# ServoCapeBareBones.net
KiCad netlist of a schematic drawn in EAGLE
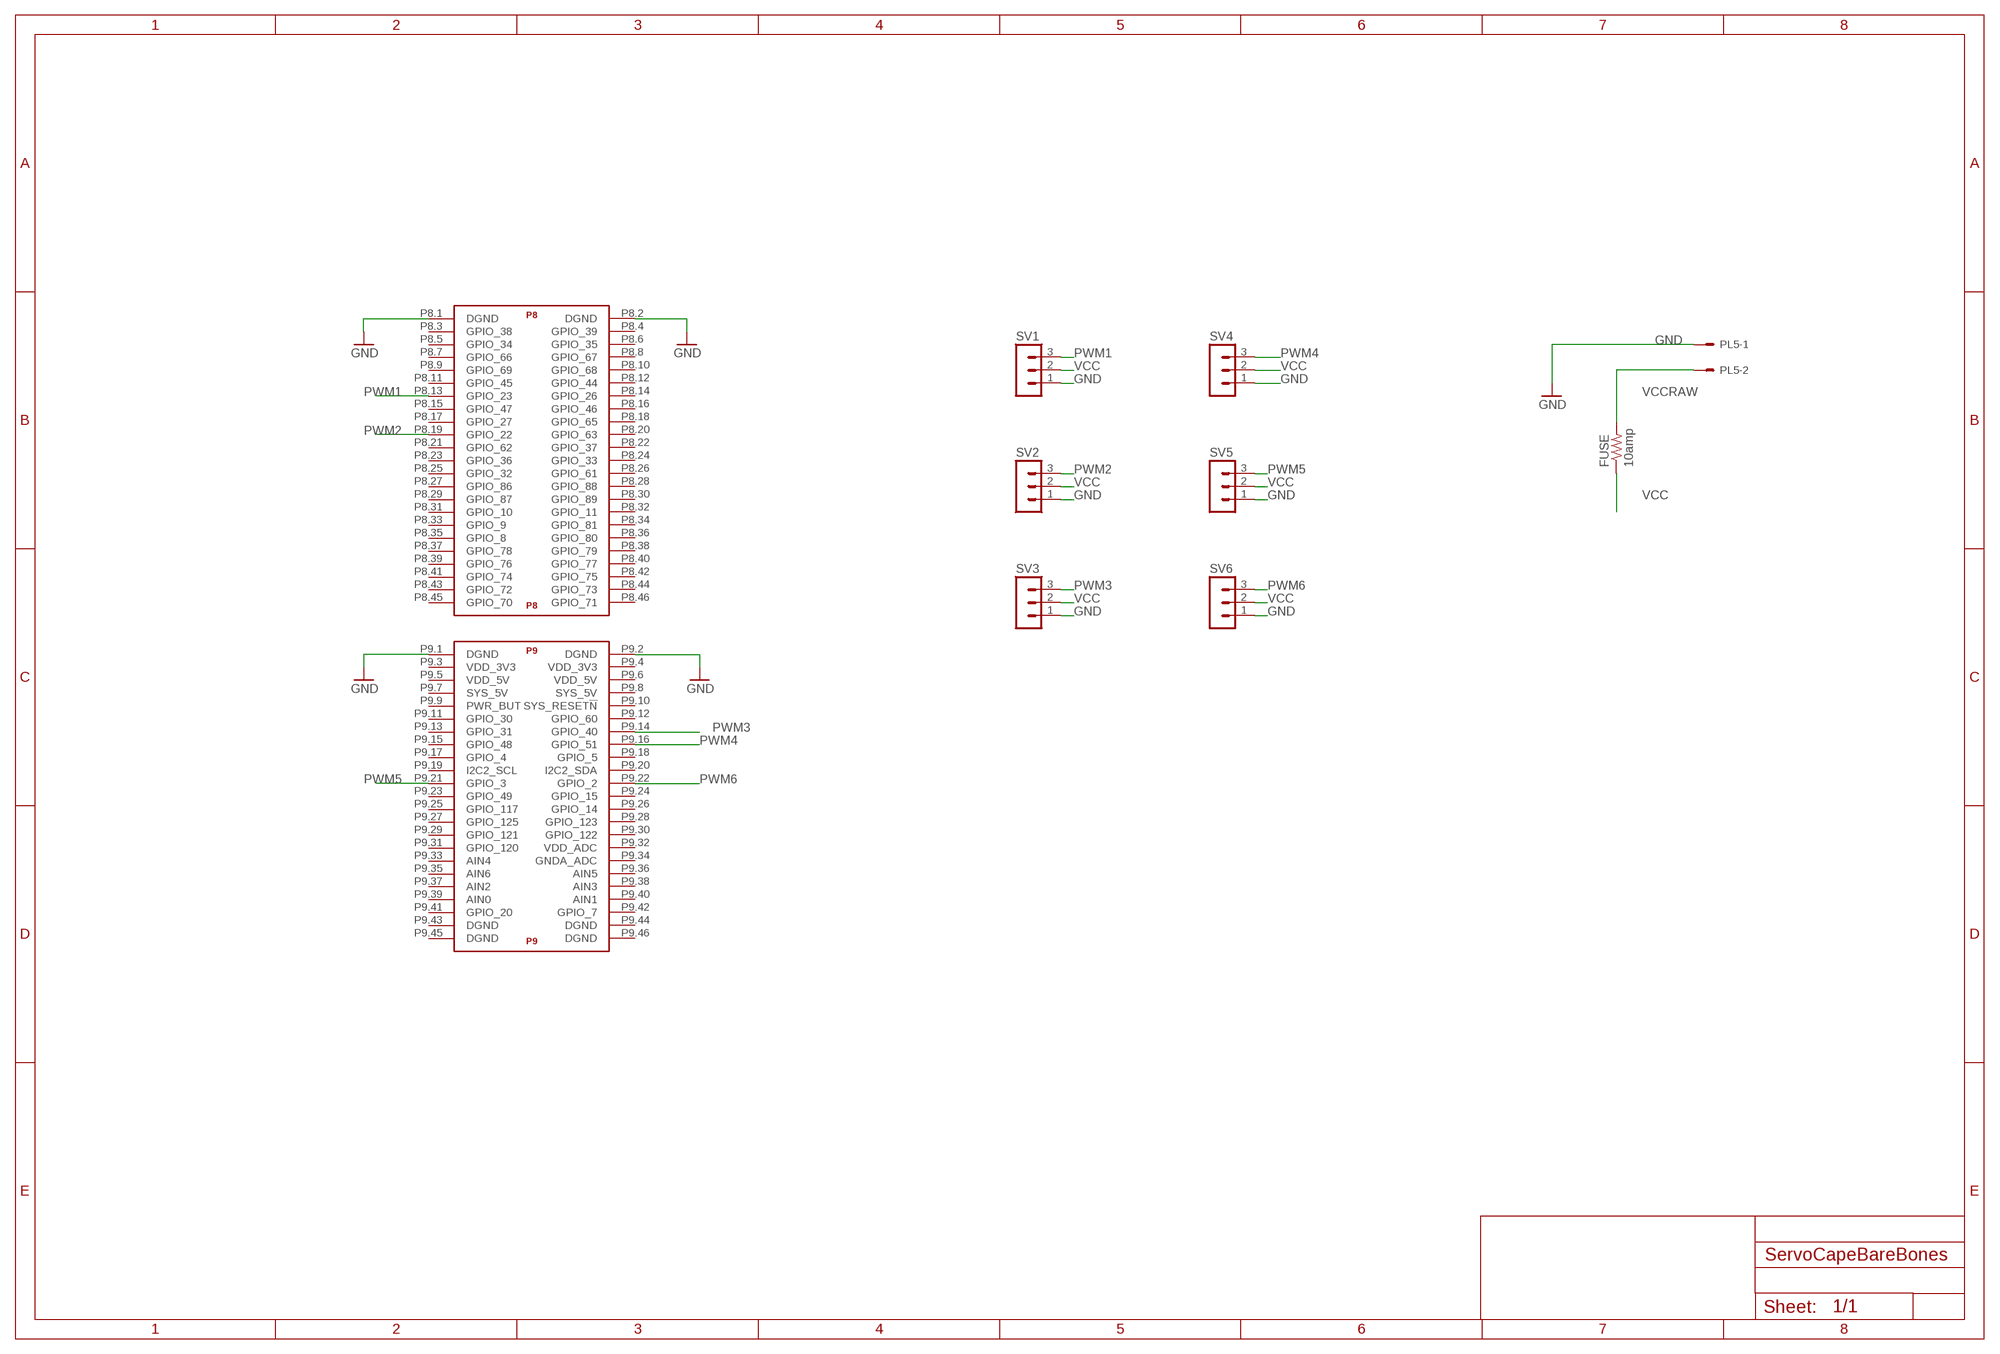
[diagram p0: schematic, sheet 1]

(export (version "E")
  (design (tool "Eeschema 10.0.6"))
  (components
    (comp (ref "FUSE")
      (value "10amp")
      (footprint "eagle-import:R1206")
      (libsource (lib "eagle-import") (part "R-US_R1206"))
    )
    (comp (ref "PL5")
      (value "555X-2H")
      (footprint "eagle-import:5569-2")
      (libsource (lib "eagle-import") (part "555X-2H"))
    )
    (comp (ref "SV1")
      (value "MA03-1")
      (footprint "eagle-import:MA03-1")
      (libsource (lib "eagle-import") (part "MA03-1"))
    )
    (comp (ref "SV2")
      (value "MA03-1")
      (footprint "eagle-import:MA03-1")
      (libsource (lib "eagle-import") (part "MA03-1"))
    )
    (comp (ref "SV3")
      (value "MA03-1")
      (footprint "eagle-import:MA03-1")
      (libsource (lib "eagle-import") (part "MA03-1"))
    )
    (comp (ref "SV4")
      (value "MA03-1")
      (footprint "eagle-import:MA03-1")
      (libsource (lib "eagle-import") (part "MA03-1"))
    )
    (comp (ref "SV5")
      (value "MA03-1")
      (footprint "eagle-import:MA03-1")
      (libsource (lib "eagle-import") (part "MA03-1"))
    )
    (comp (ref "SV6")
      (value "MA03-1")
      (footprint "eagle-import:MA03-1")
      (libsource (lib "eagle-import") (part "MA03-1"))
    )
    (comp (ref "U$1")
      (value "BEAGLE_BONE_BLACK_CAPE")
      (footprint "eagle-import:BEAGLE_BONE_BLACK_CAPE")
      (libsource (lib "eagle-import") (part "BEAGLE_BONE_BLACK_CAPE"))
    )
  )
  (nets
    (net (code "1") (name "/PWM1") (class "Default")
      (node (ref "SV1") (pin "3") (pinfunction "3_3") (pintype "passive"))
      (node (ref "U$1") (pin "P8.13") (pinfunction "GPIO_23_P8.13") (pintype "bidirectional"))
    )
    (net (code "2") (name "/PWM2") (class "Default")
      (node (ref "SV2") (pin "3") (pinfunction "3_3") (pintype "passive"))
      (node (ref "U$1") (pin "P8.19") (pinfunction "GPIO_22_P8.19") (pintype "bidirectional"))
    )
    (net (code "3") (name "/PWM3") (class "Default")
      (node (ref "SV3") (pin "3") (pinfunction "3_3") (pintype "passive"))
      (node (ref "U$1") (pin "P9.14") (pinfunction "GPIO_40_P9.14") (pintype "bidirectional"))
    )
    (net (code "4") (name "/PWM4") (class "Default")
      (node (ref "SV4") (pin "3") (pinfunction "3_3") (pintype "passive"))
      (node (ref "U$1") (pin "P9.16") (pinfunction "GPIO_51_P9.16") (pintype "bidirectional"))
    )
    (net (code "5") (name "/PWM5") (class "Default")
      (node (ref "SV5") (pin "3") (pinfunction "3_3") (pintype "passive"))
      (node (ref "U$1") (pin "P9.21") (pinfunction "GPIO_3_P9.21") (pintype "bidirectional"))
    )
    (net (code "6") (name "/PWM6") (class "Default")
      (node (ref "SV6") (pin "3") (pinfunction "3_3") (pintype "passive"))
      (node (ref "U$1") (pin "P9.22") (pinfunction "GPIO_2_P9.22") (pintype "bidirectional"))
    )
    (net (code "7") (name "/VCC") (class "Default")
      (node (ref "FUSE") (pin "1") (pinfunction "1_1") (pintype "passive"))
      (node (ref "SV1") (pin "2") (pinfunction "2_2") (pintype "passive"))
      (node (ref "SV2") (pin "2") (pinfunction "2_2") (pintype "passive"))
      (node (ref "SV3") (pin "2") (pinfunction "2_2") (pintype "passive"))
      (node (ref "SV4") (pin "2") (pinfunction "2_2") (pintype "passive"))
      (node (ref "SV5") (pin "2") (pinfunction "2_2") (pintype "passive"))
      (node (ref "SV6") (pin "2") (pinfunction "2_2") (pintype "passive"))
    )
    (net (code "8") (name "/VCCRAW") (class "Default")
      (node (ref "FUSE") (pin "2") (pinfunction "2_2") (pintype "passive"))
      (node (ref "PL5") (pin "2") (pinfunction "S_2") (pintype "passive"))
    )
    (net (code "9") (name "GND") (class "Default")
      (node (ref "PL5") (pin "1") (pinfunction "S_1") (pintype "passive"))
      (node (ref "SV1") (pin "1") (pinfunction "1_1") (pintype "passive"))
      (node (ref "SV2") (pin "1") (pinfunction "1_1") (pintype "passive"))
      (node (ref "SV3") (pin "1") (pinfunction "1_1") (pintype "passive"))
      (node (ref "SV4") (pin "1") (pinfunction "1_1") (pintype "passive"))
      (node (ref "SV5") (pin "1") (pinfunction "1_1") (pintype "passive"))
      (node (ref "SV6") (pin "1") (pinfunction "1_1") (pintype "passive"))
      (node (ref "U$1") (pin "P8.1") (pinfunction "DGND_P8.1") (pintype "bidirectional"))
      (node (ref "U$1") (pin "P8.2") (pinfunction "DGND_P8.2") (pintype "bidirectional"))
      (node (ref "U$1") (pin "P9.1") (pinfunction "DGND_P9.1") (pintype "bidirectional"))
      (node (ref "U$1") (pin "P9.2") (pinfunction "DGND_P9.2") (pintype "bidirectional"))
    )
    (net (code "10") (name "unconnected-(U$1A-GPIO_8-PadP8.35)") (class "Default")
      (node (ref "U$1") (pin "P8.35") (pinfunction "GPIO_8_P8.35") (pintype "bidirectional"))
    )
    (net (code "11") (name "unconnected-(U$1A-GPIO_9-PadP8.33)") (class "Default")
      (node (ref "U$1") (pin "P8.33") (pinfunction "GPIO_9_P8.33") (pintype "bidirectional"))
    )
    (net (code "12") (name "unconnected-(U$1A-GPIO_10-PadP8.31)") (class "Default")
      (node (ref "U$1") (pin "P8.31") (pinfunction "GPIO_10_P8.31") (pintype "bidirectional"))
    )
    (net (code "13") (name "unconnected-(U$1A-GPIO_11-PadP8.32)") (class "Default")
      (node (ref "U$1") (pin "P8.32") (pinfunction "GPIO_11_P8.32") (pintype "bidirectional"))
    )
    (net (code "14") (name "unconnected-(U$1A-GPIO_26-PadP8.14)") (class "Default")
      (node (ref "U$1") (pin "P8.14") (pinfunction "GPIO_26_P8.14") (pintype "bidirectional"))
    )
    (net (code "15") (name "unconnected-(U$1A-GPIO_27-PadP8.17)") (class "Default")
      (node (ref "U$1") (pin "P8.17") (pinfunction "GPIO_27_P8.17") (pintype "bidirectional"))
    )
    (net (code "16") (name "unconnected-(U$1A-GPIO_32-PadP8.25)") (class "Default")
      (node (ref "U$1") (pin "P8.25") (pinfunction "GPIO_32_P8.25") (pintype "bidirectional"))
    )
    (net (code "17") (name "unconnected-(U$1A-GPIO_33-PadP8.24)") (class "Default")
      (node (ref "U$1") (pin "P8.24") (pinfunction "GPIO_33_P8.24") (pintype "bidirectional"))
    )
    (net (code "18") (name "unconnected-(U$1A-GPIO_34-PadP8.5)") (class "Default")
      (node (ref "U$1") (pin "P8.5") (pinfunction "GPIO_34_P8.5") (pintype "bidirectional"))
    )
    (net (code "19") (name "unconnected-(U$1A-GPIO_35-PadP8.6)") (class "Default")
      (node (ref "U$1") (pin "P8.6") (pinfunction "GPIO_35_P8.6") (pintype "bidirectional"))
    )
    (net (code "20") (name "unconnected-(U$1A-GPIO_36-PadP8.23)") (class "Default")
      (node (ref "U$1") (pin "P8.23") (pinfunction "GPIO_36_P8.23") (pintype "bidirectional"))
    )
    (net (code "21") (name "unconnected-(U$1A-GPIO_37-PadP8.22)") (class "Default")
      (node (ref "U$1") (pin "P8.22") (pinfunction "GPIO_37_P8.22") (pintype "bidirectional"))
    )
    (net (code "22") (name "unconnected-(U$1A-GPIO_38-PadP8.3)") (class "Default")
      (node (ref "U$1") (pin "P8.3") (pinfunction "GPIO_38_P8.3") (pintype "bidirectional"))
    )
    (net (code "23") (name "unconnected-(U$1A-GPIO_39-PadP8.4)") (class "Default")
      (node (ref "U$1") (pin "P8.4") (pinfunction "GPIO_39_P8.4") (pintype "bidirectional"))
    )
    (net (code "24") (name "unconnected-(U$1A-GPIO_44-PadP8.12)") (class "Default")
      (node (ref "U$1") (pin "P8.12") (pinfunction "GPIO_44_P8.12") (pintype "bidirectional"))
    )
    (net (code "25") (name "unconnected-(U$1A-GPIO_45-PadP8.11)") (class "Default")
      (node (ref "U$1") (pin "P8.11") (pinfunction "GPIO_45_P8.11") (pintype "bidirectional"))
    )
    (net (code "26") (name "unconnected-(U$1A-GPIO_46-PadP8.16)") (class "Default")
      (node (ref "U$1") (pin "P8.16") (pinfunction "GPIO_46_P8.16") (pintype "bidirectional"))
    )
    (net (code "27") (name "unconnected-(U$1A-GPIO_47-PadP8.15)") (class "Default")
      (node (ref "U$1") (pin "P8.15") (pinfunction "GPIO_47_P8.15") (pintype "bidirectional"))
    )
    (net (code "28") (name "unconnected-(U$1A-GPIO_61-PadP8.26)") (class "Default")
      (node (ref "U$1") (pin "P8.26") (pinfunction "GPIO_61_P8.26") (pintype "bidirectional"))
    )
    (net (code "29") (name "unconnected-(U$1A-GPIO_62-PadP8.21)") (class "Default")
      (node (ref "U$1") (pin "P8.21") (pinfunction "GPIO_62_P8.21") (pintype "bidirectional"))
    )
    (net (code "30") (name "unconnected-(U$1A-GPIO_63-PadP8.20)") (class "Default")
      (node (ref "U$1") (pin "P8.20") (pinfunction "GPIO_63_P8.20") (pintype "bidirectional"))
    )
    (net (code "31") (name "unconnected-(U$1A-GPIO_65-PadP8.18)") (class "Default")
      (node (ref "U$1") (pin "P8.18") (pinfunction "GPIO_65_P8.18") (pintype "bidirectional"))
    )
    (net (code "32") (name "unconnected-(U$1A-GPIO_66-PadP8.7)") (class "Default")
      (node (ref "U$1") (pin "P8.7") (pinfunction "GPIO_66_P8.7") (pintype "bidirectional"))
    )
    (net (code "33") (name "unconnected-(U$1A-GPIO_67-PadP8.8)") (class "Default")
      (node (ref "U$1") (pin "P8.8") (pinfunction "GPIO_67_P8.8") (pintype "bidirectional"))
    )
    (net (code "34") (name "unconnected-(U$1A-GPIO_68-PadP8.10)") (class "Default")
      (node (ref "U$1") (pin "P8.10") (pinfunction "GPIO_68_P8.10") (pintype "bidirectional"))
    )
    (net (code "35") (name "unconnected-(U$1A-GPIO_69-PadP8.9)") (class "Default")
      (node (ref "U$1") (pin "P8.9") (pinfunction "GPIO_69_P8.9") (pintype "bidirectional"))
    )
    (net (code "36") (name "unconnected-(U$1A-GPIO_70-PadP8.45)") (class "Default")
      (node (ref "U$1") (pin "P8.45") (pinfunction "GPIO_70_P8.45") (pintype "bidirectional"))
    )
    (net (code "37") (name "unconnected-(U$1A-GPIO_71-PadP8.46)") (class "Default")
      (node (ref "U$1") (pin "P8.46") (pinfunction "GPIO_71_P8.46") (pintype "bidirectional"))
    )
    (net (code "38") (name "unconnected-(U$1A-GPIO_72-PadP8.43)") (class "Default")
      (node (ref "U$1") (pin "P8.43") (pinfunction "GPIO_72_P8.43") (pintype "bidirectional"))
    )
    (net (code "39") (name "unconnected-(U$1A-GPIO_73-PadP8.44)") (class "Default")
      (node (ref "U$1") (pin "P8.44") (pinfunction "GPIO_73_P8.44") (pintype "bidirectional"))
    )
    (net (code "40") (name "unconnected-(U$1A-GPIO_74-PadP8.41)") (class "Default")
      (node (ref "U$1") (pin "P8.41") (pinfunction "GPIO_74_P8.41") (pintype "bidirectional"))
    )
    (net (code "41") (name "unconnected-(U$1A-GPIO_75-PadP8.42)") (class "Default")
      (node (ref "U$1") (pin "P8.42") (pinfunction "GPIO_75_P8.42") (pintype "bidirectional"))
    )
    (net (code "42") (name "unconnected-(U$1A-GPIO_76-PadP8.39)") (class "Default")
      (node (ref "U$1") (pin "P8.39") (pinfunction "GPIO_76_P8.39") (pintype "bidirectional"))
    )
    (net (code "43") (name "unconnected-(U$1A-GPIO_77-PadP8.40)") (class "Default")
      (node (ref "U$1") (pin "P8.40") (pinfunction "GPIO_77_P8.40") (pintype "bidirectional"))
    )
    (net (code "44") (name "unconnected-(U$1A-GPIO_78-PadP8.37)") (class "Default")
      (node (ref "U$1") (pin "P8.37") (pinfunction "GPIO_78_P8.37") (pintype "bidirectional"))
    )
    (net (code "45") (name "unconnected-(U$1A-GPIO_79-PadP8.38)") (class "Default")
      (node (ref "U$1") (pin "P8.38") (pinfunction "GPIO_79_P8.38") (pintype "bidirectional"))
    )
    (net (code "46") (name "unconnected-(U$1A-GPIO_80-PadP8.36)") (class "Default")
      (node (ref "U$1") (pin "P8.36") (pinfunction "GPIO_80_P8.36") (pintype "bidirectional"))
    )
    (net (code "47") (name "unconnected-(U$1A-GPIO_81-PadP8.34)") (class "Default")
      (node (ref "U$1") (pin "P8.34") (pinfunction "GPIO_81_P8.34") (pintype "bidirectional"))
    )
    (net (code "48") (name "unconnected-(U$1A-GPIO_86-PadP8.27)") (class "Default")
      (node (ref "U$1") (pin "P8.27") (pinfunction "GPIO_86_P8.27") (pintype "bidirectional"))
    )
    (net (code "49") (name "unconnected-(U$1A-GPIO_87-PadP8.29)") (class "Default")
      (node (ref "U$1") (pin "P8.29") (pinfunction "GPIO_87_P8.29") (pintype "bidirectional"))
    )
    (net (code "50") (name "unconnected-(U$1A-GPIO_88-PadP8.28)") (class "Default")
      (node (ref "U$1") (pin "P8.28") (pinfunction "GPIO_88_P8.28") (pintype "bidirectional"))
    )
    (net (code "51") (name "unconnected-(U$1A-GPIO_89-PadP8.30)") (class "Default")
      (node (ref "U$1") (pin "P8.30") (pinfunction "GPIO_89_P8.30") (pintype "bidirectional"))
    )
    (net (code "52") (name "unconnected-(U$1B-AIN0-PadP9.39)") (class "Default")
      (node (ref "U$1") (pin "P9.39") (pinfunction "AIN0_P9.39") (pintype "bidirectional"))
    )
    (net (code "53") (name "unconnected-(U$1B-AIN1-PadP9.40)") (class "Default")
      (node (ref "U$1") (pin "P9.40") (pinfunction "AIN1_P9.40") (pintype "bidirectional"))
    )
    (net (code "54") (name "unconnected-(U$1B-AIN2-PadP9.37)") (class "Default")
      (node (ref "U$1") (pin "P9.37") (pinfunction "AIN2_P9.37") (pintype "bidirectional"))
    )
    (net (code "55") (name "unconnected-(U$1B-AIN3-PadP9.38)") (class "Default")
      (node (ref "U$1") (pin "P9.38") (pinfunction "AIN3_P9.38") (pintype "bidirectional"))
    )
    (net (code "56") (name "unconnected-(U$1B-AIN4-PadP9.33)") (class "Default")
      (node (ref "U$1") (pin "P9.33") (pinfunction "AIN4_P9.33") (pintype "bidirectional"))
    )
    (net (code "57") (name "unconnected-(U$1B-AIN5-PadP9.36)") (class "Default")
      (node (ref "U$1") (pin "P9.36") (pinfunction "AIN5_P9.36") (pintype "bidirectional"))
    )
    (net (code "58") (name "unconnected-(U$1B-AIN6-PadP9.35)") (class "Default")
      (node (ref "U$1") (pin "P9.35") (pinfunction "AIN6_P9.35") (pintype "bidirectional"))
    )
    (net (code "59") (name "unconnected-(U$1B-DGND-PadP9.43)") (class "Default")
      (node (ref "U$1") (pin "P9.43") (pinfunction "DGND_P9.43") (pintype "bidirectional"))
    )
    (net (code "60") (name "unconnected-(U$1B-DGND-PadP9.44)") (class "Default")
      (node (ref "U$1") (pin "P9.44") (pinfunction "DGND_P9.44") (pintype "bidirectional"))
    )
    (net (code "61") (name "unconnected-(U$1B-DGND-PadP9.45)") (class "Default")
      (node (ref "U$1") (pin "P9.45") (pinfunction "DGND_P9.45") (pintype "bidirectional"))
    )
    (net (code "62") (name "unconnected-(U$1B-DGND-PadP9.46)") (class "Default")
      (node (ref "U$1") (pin "P9.46") (pinfunction "DGND_P9.46") (pintype "bidirectional"))
    )
    (net (code "63") (name "unconnected-(U$1B-GNDA_ADC-PadP9.34)") (class "Default")
      (node (ref "U$1") (pin "P9.34") (pinfunction "GNDA_ADC_P9.34") (pintype "bidirectional"))
    )
    (net (code "64") (name "unconnected-(U$1B-GPIO_4-PadP9.17)") (class "Default")
      (node (ref "U$1") (pin "P9.17") (pinfunction "GPIO_4_P9.17") (pintype "bidirectional"))
    )
    (net (code "65") (name "unconnected-(U$1B-GPIO_5-PadP9.18)") (class "Default")
      (node (ref "U$1") (pin "P9.18") (pinfunction "GPIO_5_P9.18") (pintype "bidirectional"))
    )
    (net (code "66") (name "unconnected-(U$1B-GPIO_7-PadP9.42)") (class "Default")
      (node (ref "U$1") (pin "P9.42") (pinfunction "GPIO_7_P9.42") (pintype "bidirectional"))
    )
    (net (code "67") (name "unconnected-(U$1B-GPIO_14-PadP9.26)") (class "Default")
      (node (ref "U$1") (pin "P9.26") (pinfunction "GPIO_14_P9.26") (pintype "bidirectional"))
    )
    (net (code "68") (name "unconnected-(U$1B-GPIO_15-PadP9.24)") (class "Default")
      (node (ref "U$1") (pin "P9.24") (pinfunction "GPIO_15_P9.24") (pintype "bidirectional"))
    )
    (net (code "69") (name "unconnected-(U$1B-GPIO_20-PadP9.41)") (class "Default")
      (node (ref "U$1") (pin "P9.41") (pinfunction "GPIO_20_P9.41") (pintype "bidirectional"))
    )
    (net (code "70") (name "unconnected-(U$1B-GPIO_30-PadP9.11)") (class "Default")
      (node (ref "U$1") (pin "P9.11") (pinfunction "GPIO_30_P9.11") (pintype "bidirectional"))
    )
    (net (code "71") (name "unconnected-(U$1B-GPIO_31-PadP9.13)") (class "Default")
      (node (ref "U$1") (pin "P9.13") (pinfunction "GPIO_31_P9.13") (pintype "bidirectional"))
    )
    (net (code "72") (name "unconnected-(U$1B-GPIO_48-PadP9.15)") (class "Default")
      (node (ref "U$1") (pin "P9.15") (pinfunction "GPIO_48_P9.15") (pintype "bidirectional"))
    )
    (net (code "73") (name "unconnected-(U$1B-GPIO_49-PadP9.23)") (class "Default")
      (node (ref "U$1") (pin "P9.23") (pinfunction "GPIO_49_P9.23") (pintype "bidirectional"))
    )
    (net (code "74") (name "unconnected-(U$1B-GPIO_60-PadP9.12)") (class "Default")
      (node (ref "U$1") (pin "P9.12") (pinfunction "GPIO_60_P9.12") (pintype "bidirectional"))
    )
    (net (code "75") (name "unconnected-(U$1B-GPIO_117-PadP9.25)") (class "Default")
      (node (ref "U$1") (pin "P9.25") (pinfunction "GPIO_117_P9.25") (pintype "bidirectional"))
    )
    (net (code "76") (name "unconnected-(U$1B-GPIO_120-PadP9.31)") (class "Default")
      (node (ref "U$1") (pin "P9.31") (pinfunction "GPIO_120_P9.31") (pintype "bidirectional"))
    )
    (net (code "77") (name "unconnected-(U$1B-GPIO_121-PadP9.29)") (class "Default")
      (node (ref "U$1") (pin "P9.29") (pinfunction "GPIO_121_P9.29") (pintype "bidirectional"))
    )
    (net (code "78") (name "unconnected-(U$1B-GPIO_122-PadP9.30)") (class "Default")
      (node (ref "U$1") (pin "P9.30") (pinfunction "GPIO_122_P9.30") (pintype "bidirectional"))
    )
    (net (code "79") (name "unconnected-(U$1B-GPIO_123-PadP9.28)") (class "Default")
      (node (ref "U$1") (pin "P9.28") (pinfunction "GPIO_123_P9.28") (pintype "bidirectional"))
    )
    (net (code "80") (name "unconnected-(U$1B-GPIO_125-PadP9.27)") (class "Default")
      (node (ref "U$1") (pin "P9.27") (pinfunction "GPIO_125_P9.27") (pintype "bidirectional"))
    )
    (net (code "81") (name "unconnected-(U$1B-I2C2_SCL-PadP9.19)") (class "Default")
      (node (ref "U$1") (pin "P9.19") (pinfunction "I2C2_SCL_P9.19") (pintype "bidirectional"))
    )
    (net (code "82") (name "unconnected-(U$1B-I2C2_SDA-PadP9.20)") (class "Default")
      (node (ref "U$1") (pin "P9.20") (pinfunction "I2C2_SDA_P9.20") (pintype "bidirectional"))
    )
    (net (code "83") (name "unconnected-(U$1B-PWR_BUT-PadP9.9)") (class "Default")
      (node (ref "U$1") (pin "P9.9") (pinfunction "PWR_BUT_P9.9") (pintype "bidirectional"))
    )
    (net (code "84") (name "unconnected-(U$1B-SYS_5V-PadP9.7)") (class "Default")
      (node (ref "U$1") (pin "P9.7") (pinfunction "SYS_5V_P9.7") (pintype "bidirectional"))
    )
    (net (code "85") (name "unconnected-(U$1B-SYS_5V-PadP9.8)") (class "Default")
      (node (ref "U$1") (pin "P9.8") (pinfunction "SYS_5V_P9.8") (pintype "bidirectional"))
    )
    (net (code "86") (name "unconnected-(U$1B-SYS_RESET~{N}-PadP9.10)") (class "Default")
      (node (ref "U$1") (pin "P9.10") (pinfunction "SYS_RESET~{N}_P9.10") (pintype "bidirectional"))
    )
    (net (code "87") (name "unconnected-(U$1B-VDD_3V3-PadP9.3)") (class "Default")
      (node (ref "U$1") (pin "P9.3") (pinfunction "VDD_3V3_P9.3") (pintype "bidirectional"))
    )
    (net (code "88") (name "unconnected-(U$1B-VDD_3V3-PadP9.4)") (class "Default")
      (node (ref "U$1") (pin "P9.4") (pinfunction "VDD_3V3_P9.4") (pintype "bidirectional"))
    )
    (net (code "89") (name "unconnected-(U$1B-VDD_5V-PadP9.5)") (class "Default")
      (node (ref "U$1") (pin "P9.5") (pinfunction "VDD_5V_P9.5") (pintype "bidirectional"))
    )
    (net (code "90") (name "unconnected-(U$1B-VDD_5V-PadP9.6)") (class "Default")
      (node (ref "U$1") (pin "P9.6") (pinfunction "VDD_5V_P9.6") (pintype "bidirectional"))
    )
    (net (code "91") (name "unconnected-(U$1B-VDD_ADC-PadP9.32)") (class "Default")
      (node (ref "U$1") (pin "P9.32") (pinfunction "VDD_ADC_P9.32") (pintype "bidirectional"))
    )
  )
)
